# Dash_Switches_-_Small.net
KiCad netlist of a schematic drawn in EAGLE
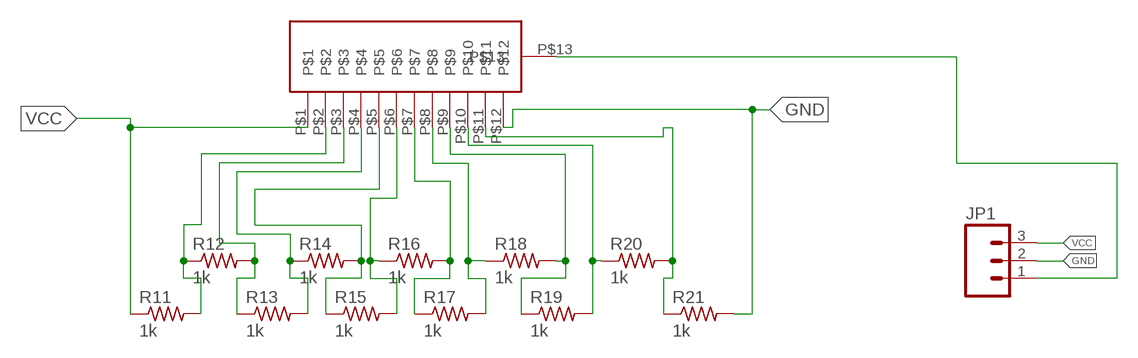
[diagram p0: schematic, sheet 1]

(export (version "E")
  (design (tool "Eeschema 10.0.6"))
  (components
    (comp (ref "JP1")
      (value "M03PTH")
      (footprint "eagle-import:1X03")
      (libsource (lib "eagle-import") (part "M03PTH"))
    )
    (comp (ref "R11")
      (value "1k")
      (footprint "eagle-import:R0603")
      (libsource (lib "eagle-import") (part "R-US_R0603"))
    )
    (comp (ref "R12")
      (value "1k")
      (footprint "eagle-import:R0603")
      (libsource (lib "eagle-import") (part "R-US_R0603"))
    )
    (comp (ref "R13")
      (value "1k")
      (footprint "eagle-import:R0603")
      (libsource (lib "eagle-import") (part "R-US_R0603"))
    )
    (comp (ref "R14")
      (value "1k")
      (footprint "eagle-import:R0603")
      (libsource (lib "eagle-import") (part "R-US_R0603"))
    )
    (comp (ref "R15")
      (value "1k")
      (footprint "eagle-import:R0603")
      (libsource (lib "eagle-import") (part "R-US_R0603"))
    )
    (comp (ref "R16")
      (value "1k")
      (footprint "eagle-import:R0603")
      (libsource (lib "eagle-import") (part "R-US_R0603"))
    )
    (comp (ref "R17")
      (value "1k")
      (footprint "eagle-import:R0603")
      (libsource (lib "eagle-import") (part "R-US_R0603"))
    )
    (comp (ref "R18")
      (value "1k")
      (footprint "eagle-import:R0603")
      (libsource (lib "eagle-import") (part "R-US_R0603"))
    )
    (comp (ref "R19")
      (value "1k")
      (footprint "eagle-import:R0603")
      (libsource (lib "eagle-import") (part "R-US_R0603"))
    )
    (comp (ref "R20")
      (value "1k")
      (footprint "eagle-import:R0603")
      (libsource (lib "eagle-import") (part "R-US_R0603"))
    )
    (comp (ref "R21")
      (value "1k")
      (footprint "eagle-import:R0603")
      (libsource (lib "eagle-import") (part "R-US_R0603"))
    )
    (comp (ref "U$2")
      (value "ROTSWITCH")
      (footprint "eagle-import:ROTSWITCH")
      (libsource (lib "eagle-import") (part "ROTSWITCH"))
    )
  )
  (nets
    (net (code "1") (name "GND") (class "Default")
      (node (ref "JP1") (pin "2") (pinfunction "2_2") (pintype "passive"))
      (node (ref "R21") (pin "2") (pinfunction "2_2") (pintype "passive"))
      (node (ref "U$2") (pin "P$12") (pinfunction "P$12_P$12") (pintype "bidirectional"))
    )
    (net (code "2") (name "Net-(JP1-Pad1)") (class "Default")
      (node (ref "JP1") (pin "1") (pinfunction "1_1") (pintype "passive"))
      (node (ref "U$2") (pin "P$13") (pinfunction "P$13_P$13") (pintype "bidirectional"))
    )
    (net (code "3") (name "Net-(R11-Pad2)") (class "Default")
      (node (ref "R11") (pin "2") (pinfunction "2_2") (pintype "passive"))
      (node (ref "R12") (pin "1") (pinfunction "1_1") (pintype "passive"))
      (node (ref "U$2") (pin "P$2") (pinfunction "P$2_P$2") (pintype "bidirectional"))
    )
    (net (code "4") (name "Net-(R12-Pad2)") (class "Default")
      (node (ref "R12") (pin "2") (pinfunction "2_2") (pintype "passive"))
      (node (ref "R13") (pin "1") (pinfunction "1_1") (pintype "passive"))
      (node (ref "U$2") (pin "P$3") (pinfunction "P$3_P$3") (pintype "bidirectional"))
    )
    (net (code "5") (name "Net-(R13-Pad2)") (class "Default")
      (node (ref "R13") (pin "2") (pinfunction "2_2") (pintype "passive"))
      (node (ref "R14") (pin "1") (pinfunction "1_1") (pintype "passive"))
      (node (ref "U$2") (pin "P$4") (pinfunction "P$4_P$4") (pintype "bidirectional"))
    )
    (net (code "6") (name "Net-(R14-Pad2)") (class "Default")
      (node (ref "R14") (pin "2") (pinfunction "2_2") (pintype "passive"))
      (node (ref "R15") (pin "1") (pinfunction "1_1") (pintype "passive"))
      (node (ref "U$2") (pin "P$5") (pinfunction "P$5_P$5") (pintype "bidirectional"))
    )
    (net (code "7") (name "Net-(R15-Pad2)") (class "Default")
      (node (ref "R15") (pin "2") (pinfunction "2_2") (pintype "passive"))
      (node (ref "R16") (pin "1") (pinfunction "1_1") (pintype "passive"))
      (node (ref "U$2") (pin "P$6") (pinfunction "P$6_P$6") (pintype "bidirectional"))
    )
    (net (code "8") (name "Net-(R16-Pad2)") (class "Default")
      (node (ref "R16") (pin "2") (pinfunction "2_2") (pintype "passive"))
      (node (ref "R17") (pin "1") (pinfunction "1_1") (pintype "passive"))
      (node (ref "U$2") (pin "P$7") (pinfunction "P$7_P$7") (pintype "bidirectional"))
    )
    (net (code "9") (name "Net-(R17-Pad2)") (class "Default")
      (node (ref "R17") (pin "2") (pinfunction "2_2") (pintype "passive"))
      (node (ref "R18") (pin "1") (pinfunction "1_1") (pintype "passive"))
      (node (ref "U$2") (pin "P$8") (pinfunction "P$8_P$8") (pintype "bidirectional"))
    )
    (net (code "10") (name "Net-(R18-Pad2)") (class "Default")
      (node (ref "R18") (pin "2") (pinfunction "2_2") (pintype "passive"))
      (node (ref "R19") (pin "1") (pinfunction "1_1") (pintype "passive"))
      (node (ref "U$2") (pin "P$9") (pinfunction "P$9_P$9") (pintype "bidirectional"))
    )
    (net (code "11") (name "Net-(R19-Pad2)") (class "Default")
      (node (ref "R19") (pin "2") (pinfunction "2_2") (pintype "passive"))
      (node (ref "R20") (pin "1") (pinfunction "1_1") (pintype "passive"))
      (node (ref "U$2") (pin "P$10") (pinfunction "P$10_P$10") (pintype "bidirectional"))
    )
    (net (code "12") (name "Net-(R20-Pad2)") (class "Default")
      (node (ref "R20") (pin "2") (pinfunction "2_2") (pintype "passive"))
      (node (ref "R21") (pin "1") (pinfunction "1_1") (pintype "passive"))
      (node (ref "U$2") (pin "P$11") (pinfunction "P$11_P$11") (pintype "bidirectional"))
    )
    (net (code "13") (name "VCC") (class "Default")
      (node (ref "JP1") (pin "3") (pinfunction "3_3") (pintype "passive"))
      (node (ref "R11") (pin "1") (pinfunction "1_1") (pintype "passive"))
      (node (ref "U$2") (pin "P$1") (pinfunction "P$1_P$1") (pintype "bidirectional"))
    )
  )
)
